# minimumduino-uno.net
KiCad netlist of a schematic drawn in EAGLE
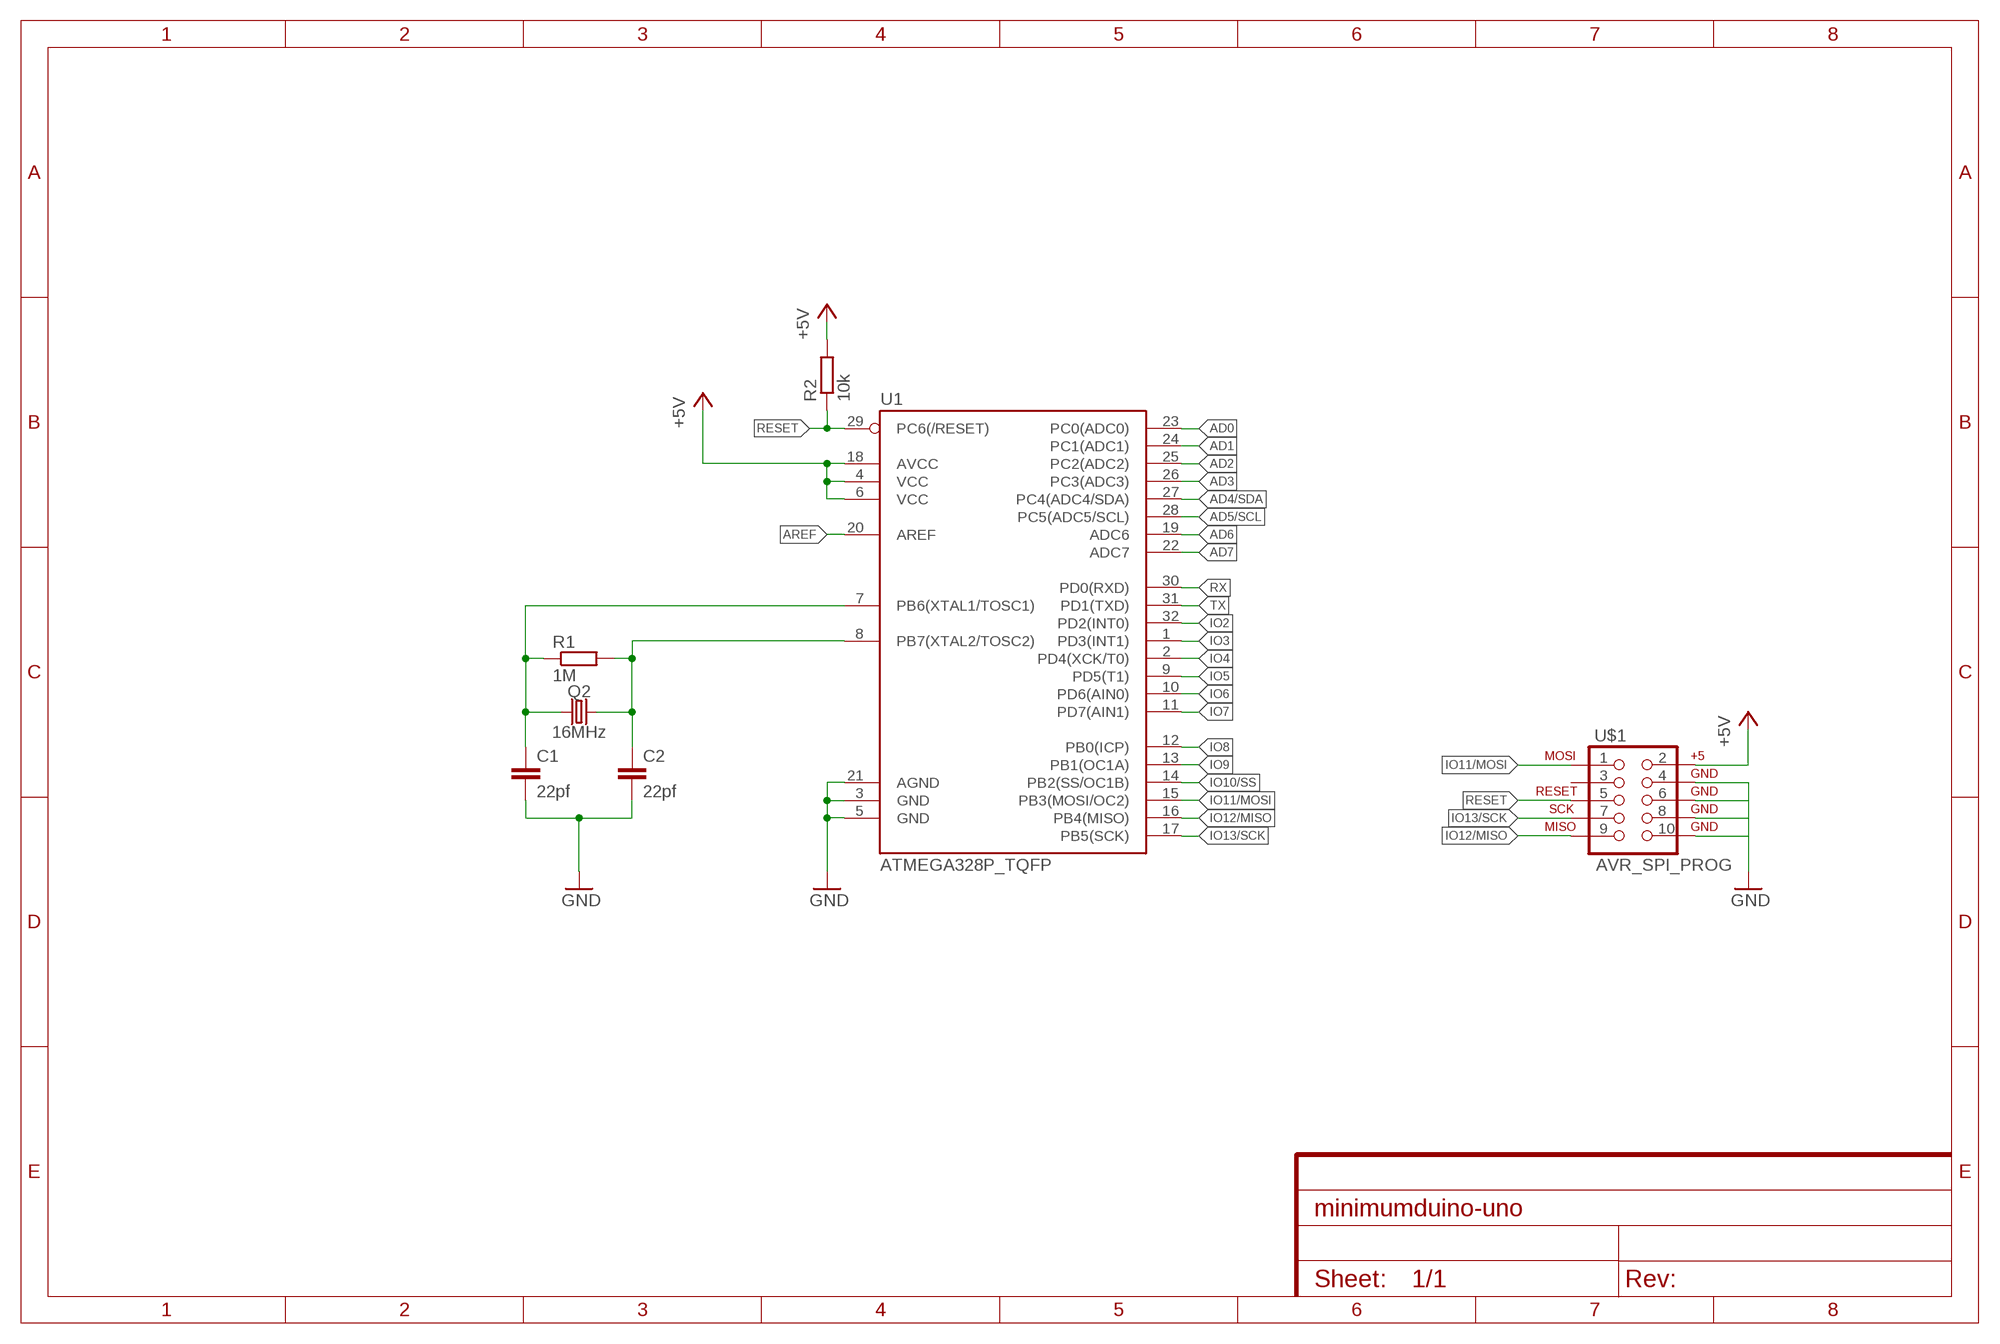
[diagram p0: schematic, sheet 1]

(export (version "E")
  (design (tool "Eeschema 10.0.6"))
  (components
    (comp (ref "C1")
      (value "22pf")
      (footprint "eagle-import:C1206")
      (libsource (lib "eagle-import") (part "C-EUC1206"))
    )
    (comp (ref "C2")
      (value "22pf")
      (footprint "eagle-import:C1206")
      (libsource (lib "eagle-import") (part "C-EUC1206"))
    )
    (comp (ref "Q2")
      (value "16MHz")
      (footprint "eagle-import:HC49U")
      (libsource (lib "eagle-import") (part "CRYSTALPTH-HC49UV"))
    )
    (comp (ref "R1")
      (value "1M")
      (footprint "eagle-import:R1206")
      (libsource (lib "eagle-import") (part "R-EU_R1206"))
    )
    (comp (ref "R2")
      (value "10k")
      (footprint "eagle-import:R1206")
      (libsource (lib "eagle-import") (part "R-EU_R1206"))
    )
    (comp (ref "U$1")
      (value "AVR_SPI_PROG")
      (footprint "eagle-import:AVR_ICSP")
      (libsource (lib "eagle-import") (part "AVR_SPI_PROG"))
    )
    (comp (ref "U1")
      (value "ATMEGA328P_TQFP")
      (footprint "eagle-import:TQFP32-08")
      (libsource (lib "eagle-import") (part "ATMEGA328P_TQFP"))
    )
  )
  (nets
    (net (code "1") (name "+5V") (class "Default")
      (node (ref "R2") (pin "2") (pinfunction "2_2") (pintype "passive"))
      (node (ref "U$1") (pin "2") (pinfunction "2_2") (pintype "passive"))
      (node (ref "U1") (pin "18") (pinfunction "AVCC_18") (pintype "bidirectional"))
      (node (ref "U1") (pin "4") (pinfunction "VCC_4") (pintype "bidirectional"))
      (node (ref "U1") (pin "6") (pinfunction "VCC_6") (pintype "bidirectional"))
    )
    (net (code "2") (name "AD0") (class "Default")
      (node (ref "U1") (pin "23") (pinfunction "PC0(ADC0)_23") (pintype "bidirectional"))
    )
    (net (code "3") (name "AD1") (class "Default")
      (node (ref "U1") (pin "24") (pinfunction "PC1(ADC1)_24") (pintype "bidirectional"))
    )
    (net (code "4") (name "AD2") (class "Default")
      (node (ref "U1") (pin "25") (pinfunction "PC2(ADC2)_25") (pintype "bidirectional"))
    )
    (net (code "5") (name "AD3") (class "Default")
      (node (ref "U1") (pin "26") (pinfunction "PC3(ADC3)_26") (pintype "bidirectional"))
    )
    (net (code "6") (name "AD4{slash}SDA") (class "Default")
      (node (ref "U1") (pin "27") (pinfunction "PC4(ADC4/SDA)_27") (pintype "bidirectional"))
    )
    (net (code "7") (name "AD5{slash}SCL") (class "Default")
      (node (ref "U1") (pin "28") (pinfunction "PC5(ADC5/SCL)_28") (pintype "bidirectional"))
    )
    (net (code "8") (name "AD6") (class "Default")
      (node (ref "U1") (pin "19") (pinfunction "ADC6_19") (pintype "bidirectional"))
    )
    (net (code "9") (name "AD7") (class "Default")
      (node (ref "U1") (pin "22") (pinfunction "ADC7_22") (pintype "bidirectional"))
    )
    (net (code "10") (name "AREF") (class "Default")
      (node (ref "U1") (pin "20") (pinfunction "AREF_20") (pintype "bidirectional"))
    )
    (net (code "11") (name "GND") (class "Default")
      (node (ref "C1") (pin "2") (pinfunction "2_2") (pintype "passive"))
      (node (ref "C2") (pin "2") (pinfunction "2_2") (pintype "passive"))
      (node (ref "U$1") (pin "10") (pinfunction "10_10") (pintype "passive"))
      (node (ref "U$1") (pin "4") (pinfunction "4_4") (pintype "passive"))
      (node (ref "U$1") (pin "6") (pinfunction "6_6") (pintype "passive"))
      (node (ref "U$1") (pin "8") (pinfunction "8_8") (pintype "passive"))
      (node (ref "U1") (pin "21") (pinfunction "AGND_21") (pintype "bidirectional"))
      (node (ref "U1") (pin "3") (pinfunction "GND_3") (pintype "bidirectional"))
      (node (ref "U1") (pin "5") (pinfunction "GND_5") (pintype "bidirectional"))
    )
    (net (code "12") (name "IO2") (class "Default")
      (node (ref "U1") (pin "32") (pinfunction "PD2(INT0)_32") (pintype "bidirectional"))
    )
    (net (code "13") (name "IO3") (class "Default")
      (node (ref "U1") (pin "1") (pinfunction "PD3(INT1)_1") (pintype "bidirectional"))
    )
    (net (code "14") (name "IO4") (class "Default")
      (node (ref "U1") (pin "2") (pinfunction "PD4(XCK/T0)_2") (pintype "bidirectional"))
    )
    (net (code "15") (name "IO5") (class "Default")
      (node (ref "U1") (pin "9") (pinfunction "PD5(T1)_9") (pintype "bidirectional"))
    )
    (net (code "16") (name "IO6") (class "Default")
      (node (ref "U1") (pin "10") (pinfunction "PD6(AIN0)_10") (pintype "bidirectional"))
    )
    (net (code "17") (name "IO7") (class "Default")
      (node (ref "U1") (pin "11") (pinfunction "PD7(AIN1)_11") (pintype "bidirectional"))
    )
    (net (code "18") (name "IO8") (class "Default")
      (node (ref "U1") (pin "12") (pinfunction "PB0(ICP)_12") (pintype "bidirectional"))
    )
    (net (code "19") (name "IO9") (class "Default")
      (node (ref "U1") (pin "13") (pinfunction "PB1(OC1A)_13") (pintype "bidirectional"))
    )
    (net (code "20") (name "IO10{slash}SS") (class "Default")
      (node (ref "U1") (pin "14") (pinfunction "PB2(SS/OC1B)_14") (pintype "bidirectional"))
    )
    (net (code "21") (name "IO11{slash}MOSI") (class "Default")
      (node (ref "U$1") (pin "1") (pinfunction "1_1") (pintype "passive"))
      (node (ref "U1") (pin "15") (pinfunction "PB3(MOSI/OC2)_15") (pintype "bidirectional"))
    )
    (net (code "22") (name "IO12{slash}MISO") (class "Default")
      (node (ref "U$1") (pin "9") (pinfunction "9_9") (pintype "passive"))
      (node (ref "U1") (pin "16") (pinfunction "PB4(MISO)_16") (pintype "bidirectional"))
    )
    (net (code "23") (name "IO13{slash}SCK") (class "Default")
      (node (ref "U$1") (pin "7") (pinfunction "7_7") (pintype "passive"))
      (node (ref "U1") (pin "17") (pinfunction "PB5(SCK)_17") (pintype "bidirectional"))
    )
    (net (code "24") (name "Net-(U1-PB6(XTAL1{slash}TOSC1))") (class "Default")
      (node (ref "C1") (pin "1") (pinfunction "1_1") (pintype "passive"))
      (node (ref "Q2") (pin "1") (pinfunction "1_1") (pintype "passive"))
      (node (ref "R1") (pin "1") (pinfunction "1_1") (pintype "passive"))
      (node (ref "U1") (pin "7") (pinfunction "PB6(XTAL1/TOSC1)_7") (pintype "bidirectional"))
    )
    (net (code "25") (name "Net-(U1-PB7(XTAL2{slash}TOSC2))") (class "Default")
      (node (ref "C2") (pin "1") (pinfunction "1_1") (pintype "passive"))
      (node (ref "Q2") (pin "2") (pinfunction "2_2") (pintype "passive"))
      (node (ref "R1") (pin "2") (pinfunction "2_2") (pintype "passive"))
      (node (ref "U1") (pin "8") (pinfunction "PB7(XTAL2/TOSC2)_8") (pintype "bidirectional"))
    )
    (net (code "26") (name "RESET") (class "Default")
      (node (ref "R2") (pin "1") (pinfunction "1_1") (pintype "passive"))
      (node (ref "U$1") (pin "5") (pinfunction "5_5") (pintype "passive"))
      (node (ref "U1") (pin "29") (pinfunction "PC6(/RESET)_29") (pintype "bidirectional"))
    )
    (net (code "27") (name "RX") (class "Default")
      (node (ref "U1") (pin "30") (pinfunction "PD0(RXD)_30") (pintype "bidirectional"))
    )
    (net (code "28") (name "TX") (class "Default")
      (node (ref "U1") (pin "31") (pinfunction "PD1(TXD)_31") (pintype "bidirectional"))
    )
    (net (code "29") (name "unconnected-(U$1-Pad3)") (class "Default")
      (node (ref "U$1") (pin "3") (pinfunction "3_3") (pintype "passive"))
    )
  )
)
